# Starter.net
KiCad netlist of a schematic drawn in EAGLE
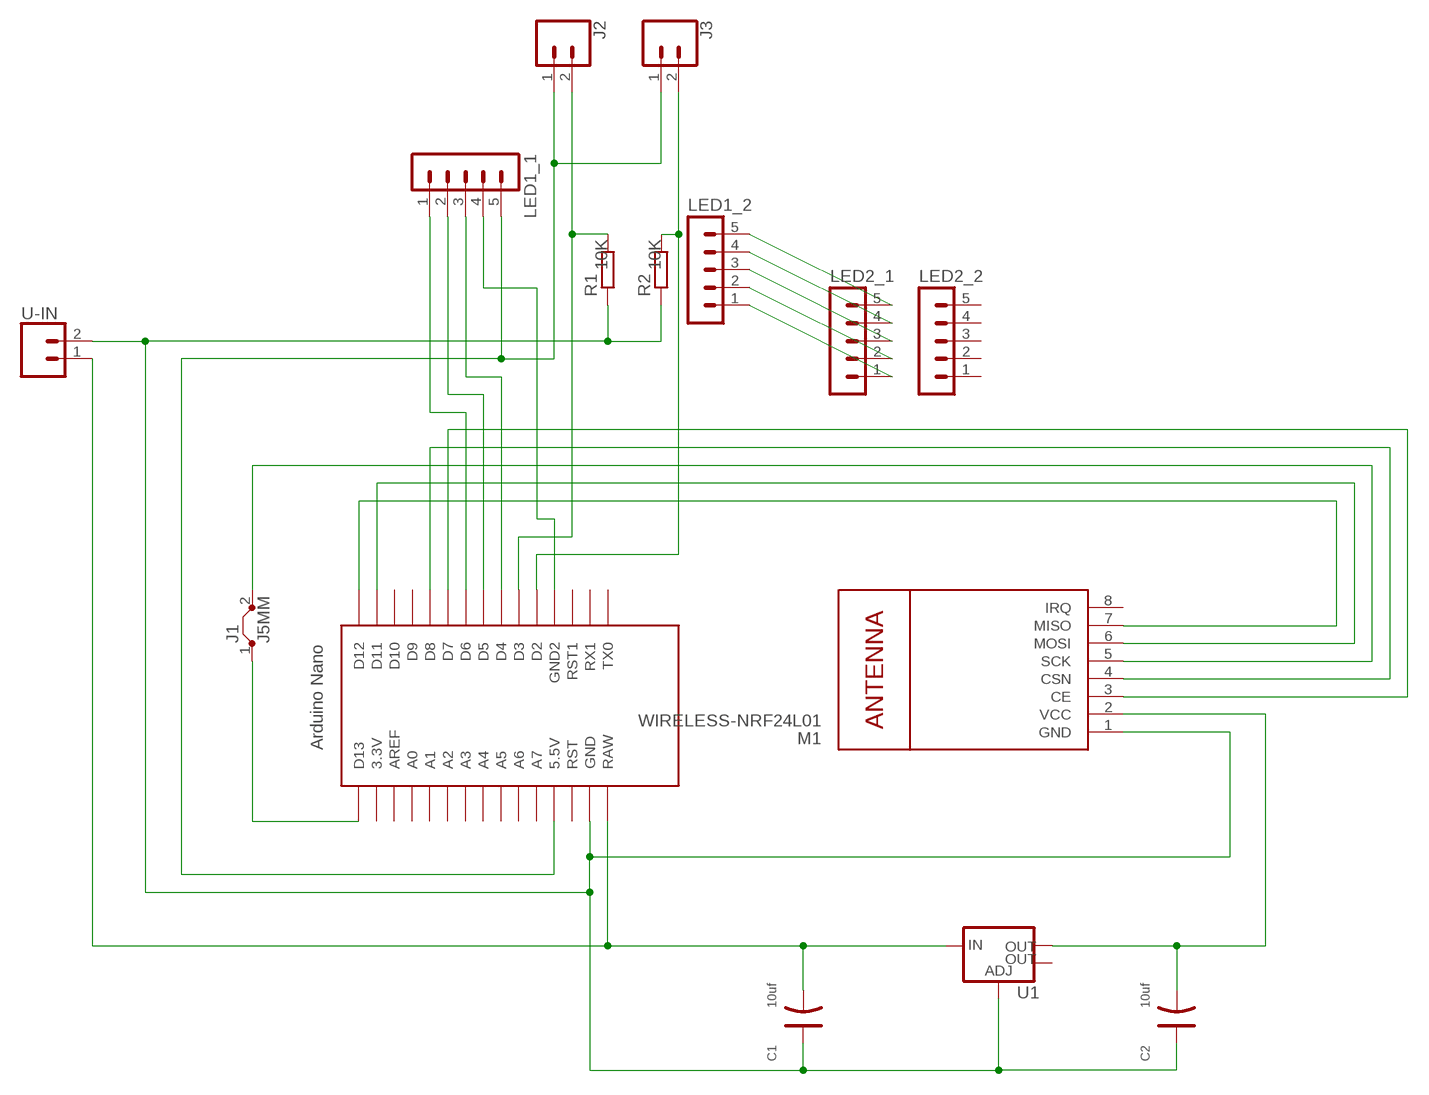
[diagram p0: schematic, sheet 1]

(export (version "E")
  (design (tool "Eeschema 10.0.6"))
  (components
    (comp (ref "C1")
      (value "10uf")
      (footprint "eagle-import:AVX-B")
      (fields (field (name "MPN") "TAJB106K016RNJ"))
      (libsource (lib "eagle-import") (part "TANTALUM-SMD-10UF-16V-10%(AVX-B)"))
    )
    (comp (ref "C2")
      (value "10uf")
      (footprint "eagle-import:AVX-B")
      (fields (field (name "MPN") "TAJB106K016RNJ"))
      (libsource (lib "eagle-import") (part "TANTALUM-SMD-10UF-16V-10%(AVX-B)"))
    )
    (comp (ref "J1")
      (value "J5MM")
      (footprint "eagle-import:05")
      (libsource (lib "eagle-import") (part "J5MM"))
    )
    (comp (ref "J2")
      (value "CONN_025MM")
      (footprint "eagle-import:SCREWTERMINAL-5MM-2")
      (libsource (lib "eagle-import") (part "CONN_025MM"))
    )
    (comp (ref "J3")
      (value "CONN_025MM")
      (footprint "eagle-import:SCREWTERMINAL-5MM-2")
      (libsource (lib "eagle-import") (part "CONN_025MM"))
    )
    (comp (ref "LED1_1")
      (value "MA05-1")
      (footprint "eagle-import:MA05-1")
      (libsource (lib "eagle-import") (part "MA05-1"))
    )
    (comp (ref "LED1_2")
      (value "MA05-1")
      (footprint "eagle-import:MA05-1")
      (libsource (lib "eagle-import") (part "MA05-1"))
    )
    (comp (ref "LED2_1")
      (value "MA05-1")
      (footprint "eagle-import:MA05-1")
      (libsource (lib "eagle-import") (part "MA05-1"))
    )
    (comp (ref "LED2_2")
      (value "MA05-1")
      (footprint "eagle-import:MA05-1")
      (libsource (lib "eagle-import") (part "MA05-1"))
    )
    (comp (ref "M1")
      (value "WIRELESS-NRF24L01")
      (footprint "eagle-import:WIRELESS-NRF24L01")
      (libsource (lib "eagle-import") (part "WIRELESS-NRF24L01"))
    )
    (comp (ref "R1")
      (value "R-EU_0207/12")
      (footprint "eagle-import:0207_12")
      (fields (field (name "R") "10K"))
      (libsource (lib "eagle-import") (part "R-EU_0207/12"))
    )
    (comp (ref "R2")
      (value "R-EU_0207/12")
      (footprint "eagle-import:0207_12")
      (fields (field (name "R") "10K"))
      (libsource (lib "eagle-import") (part "R-EU_0207/12"))
    )
    (comp (ref "U$1")
      (value "NANO")
      (footprint "eagle-import:NANO")
      (libsource (lib "eagle-import") (part "NANO"))
    )
    (comp (ref "U-IN")
      (value "CONN_025MM")
      (footprint "eagle-import:SCREWTERMINAL-5MM-2")
      (libsource (lib "eagle-import") (part "CONN_025MM"))
    )
    (comp (ref "U1")
      (value "V_REG_LM1117SOT223")
      (footprint "eagle-import:SOT223")
      (libsource (lib "eagle-import") (part "V_REG_LM1117SOT223"))
    )
  )
  (nets
    (net (code "1") (name "Net-(J1-Pad1)") (class "Default")
      (node (ref "J1") (pin "1") (pinfunction "1_1") (pintype "passive"))
      (node (ref "U$1") (pin "D13") (pinfunction "D13_D13") (pintype "bidirectional"))
    )
    (net (code "2") (name "Net-(J2-Pad2)") (class "Default")
      (node (ref "J2") (pin "2") (pinfunction "2_2") (pintype "passive"))
      (node (ref "R1") (pin "2") (pinfunction "2_2") (pintype "passive"))
      (node (ref "U$1") (pin "D3") (pinfunction "D3_D3") (pintype "bidirectional"))
    )
    (net (code "3") (name "Net-(J3-Pad2)") (class "Default")
      (node (ref "J3") (pin "2") (pinfunction "2_2") (pintype "passive"))
      (node (ref "R2") (pin "2") (pinfunction "2_2") (pintype "passive"))
      (node (ref "U$1") (pin "D2") (pinfunction "D2_D2") (pintype "bidirectional"))
    )
    (net (code "4") (name "Net-(LED1_1-Pad1)") (class "Default")
      (node (ref "LED1_1") (pin "1") (pinfunction "1_1") (pintype "passive"))
      (node (ref "U$1") (pin "D6") (pinfunction "D6_D6") (pintype "bidirectional"))
    )
    (net (code "5") (name "Net-(LED1_1-Pad2)") (class "Default")
      (node (ref "LED1_1") (pin "2") (pinfunction "2_2") (pintype "passive"))
      (node (ref "U$1") (pin "D5") (pinfunction "D5_D5") (pintype "bidirectional"))
    )
    (net (code "6") (name "Net-(LED1_1-Pad3)") (class "Default")
      (node (ref "LED1_1") (pin "3") (pinfunction "3_3") (pintype "passive"))
      (node (ref "U$1") (pin "D4") (pinfunction "D4_D4") (pintype "bidirectional"))
    )
    (net (code "7") (name "Net-(LED1_2-Pad1)") (class "Default")
      (node (ref "LED1_2") (pin "1") (pinfunction "1_1") (pintype "passive"))
      (node (ref "LED2_1") (pin "1") (pinfunction "1_1") (pintype "passive"))
    )
    (net (code "8") (name "Net-(LED1_2-Pad2)") (class "Default")
      (node (ref "LED1_2") (pin "2") (pinfunction "2_2") (pintype "passive"))
      (node (ref "LED2_1") (pin "2") (pinfunction "2_2") (pintype "passive"))
    )
    (net (code "9") (name "Net-(LED1_2-Pad3)") (class "Default")
      (node (ref "LED1_2") (pin "3") (pinfunction "3_3") (pintype "passive"))
      (node (ref "LED2_1") (pin "3") (pinfunction "3_3") (pintype "passive"))
    )
    (net (code "10") (name "Net-(LED1_2-Pad4)") (class "Default")
      (node (ref "LED1_2") (pin "4") (pinfunction "4_4") (pintype "passive"))
      (node (ref "LED2_1") (pin "4") (pinfunction "4_4") (pintype "passive"))
    )
    (net (code "11") (name "Net-(LED1_2-Pad5)") (class "Default")
      (node (ref "LED1_2") (pin "5") (pinfunction "5_5") (pintype "passive"))
      (node (ref "LED2_1") (pin "5") (pinfunction "5_5") (pintype "passive"))
    )
    (net (code "12") (name "Net-(M1-CE)") (class "Default")
      (node (ref "M1") (pin "3") (pinfunction "CE_3") (pintype "bidirectional"))
      (node (ref "U$1") (pin "D7") (pinfunction "D7_D7") (pintype "bidirectional"))
    )
    (net (code "13") (name "Net-(M1-CSN)") (class "Default")
      (node (ref "M1") (pin "4") (pinfunction "CSN_4") (pintype "bidirectional"))
      (node (ref "U$1") (pin "D8") (pinfunction "D8_D8") (pintype "bidirectional"))
    )
    (net (code "14") (name "Net-(M1-GND)") (class "Default")
      (node (ref "C1") (pin "+") (pinfunction "+_+") (pintype "passive"))
      (node (ref "C2") (pin "+") (pinfunction "+_+") (pintype "passive"))
      (node (ref "M1") (pin "1") (pinfunction "GND_1") (pintype "power_in"))
      (node (ref "R1") (pin "1") (pinfunction "1_1") (pintype "passive"))
      (node (ref "R2") (pin "1") (pinfunction "1_1") (pintype "passive"))
      (node (ref "U$1") (pin "GND") (pinfunction "GND_GND") (pintype "bidirectional"))
      (node (ref "U-IN") (pin "2") (pinfunction "2_2") (pintype "passive"))
      (node (ref "U1") (pin "1") (pinfunction "ADJ_1") (pintype "input"))
    )
    (net (code "15") (name "Net-(M1-MISO)") (class "Default")
      (node (ref "M1") (pin "7") (pinfunction "MISO_7") (pintype "bidirectional"))
      (node (ref "U$1") (pin "D12") (pinfunction "D12_D12") (pintype "bidirectional"))
    )
    (net (code "16") (name "Net-(M1-MOSI)") (class "Default")
      (node (ref "M1") (pin "6") (pinfunction "MOSI_6") (pintype "bidirectional"))
      (node (ref "U$1") (pin "D11") (pinfunction "D11_D11") (pintype "bidirectional"))
    )
    (net (code "17") (name "Net-(M1-SCK)") (class "Default")
      (node (ref "J1") (pin "2") (pinfunction "2_2") (pintype "passive"))
      (node (ref "M1") (pin "5") (pinfunction "SCK_5") (pintype "bidirectional"))
    )
    (net (code "18") (name "Net-(M1-VCC)") (class "Default")
      (node (ref "C2") (pin "-") (pinfunction "-_-") (pintype "passive"))
      (node (ref "M1") (pin "2") (pinfunction "VCC_2") (pintype "power_in"))
      (node (ref "U1") (pin "2") (pinfunction "OUT_2") (pintype "output"))
    )
    (net (code "19") (name "Net-(U$1-5.5V)") (class "Default")
      (node (ref "J2") (pin "1") (pinfunction "1_1") (pintype "passive"))
      (node (ref "J3") (pin "1") (pinfunction "1_1") (pintype "passive"))
      (node (ref "LED1_1") (pin "5") (pinfunction "5_5") (pintype "passive"))
      (node (ref "U$1") (pin "5V") (pinfunction "5.5V_5V") (pintype "bidirectional"))
    )
    (net (code "20") (name "Net-(U$1-GND2)") (class "Default")
      (node (ref "LED1_1") (pin "4") (pinfunction "4_4") (pintype "passive"))
      (node (ref "U$1") (pin "GND1") (pinfunction "GND2_GND1") (pintype "bidirectional"))
    )
    (net (code "21") (name "Net-(U1-IN)") (class "Default")
      (node (ref "C1") (pin "-") (pinfunction "-_-") (pintype "passive"))
      (node (ref "U$1") (pin "RAW") (pinfunction "RAW_RAW") (pintype "bidirectional"))
      (node (ref "U-IN") (pin "1") (pinfunction "1_1") (pintype "passive"))
      (node (ref "U1") (pin "3") (pinfunction "IN_3") (pintype "input"))
    )
    (net (code "22") (name "unconnected-(LED2_2-Pad1)") (class "Default")
      (node (ref "LED2_2") (pin "1") (pinfunction "1_1") (pintype "passive"))
    )
    (net (code "23") (name "unconnected-(LED2_2-Pad2)") (class "Default")
      (node (ref "LED2_2") (pin "2") (pinfunction "2_2") (pintype "passive"))
    )
    (net (code "24") (name "unconnected-(LED2_2-Pad3)") (class "Default")
      (node (ref "LED2_2") (pin "3") (pinfunction "3_3") (pintype "passive"))
    )
    (net (code "25") (name "unconnected-(LED2_2-Pad4)") (class "Default")
      (node (ref "LED2_2") (pin "4") (pinfunction "4_4") (pintype "passive"))
    )
    (net (code "26") (name "unconnected-(LED2_2-Pad5)") (class "Default")
      (node (ref "LED2_2") (pin "5") (pinfunction "5_5") (pintype "passive"))
    )
    (net (code "27") (name "unconnected-(M1-IRQ-Pad8)") (class "Default")
      (node (ref "M1") (pin "8") (pinfunction "IRQ_8") (pintype "bidirectional"))
    )
    (net (code "28") (name "unconnected-(U$1-Pad3.3V)") (class "Default")
      (node (ref "U$1") (pin "3.3V") (pinfunction "3.3V_3.3V") (pintype "bidirectional"))
    )
    (net (code "29") (name "unconnected-(U$1-PadA0)") (class "Default")
      (node (ref "U$1") (pin "A0") (pinfunction "A0_A0") (pintype "bidirectional"))
    )
    (net (code "30") (name "unconnected-(U$1-PadA1)") (class "Default")
      (node (ref "U$1") (pin "A1") (pinfunction "A1_A1") (pintype "bidirectional"))
    )
    (net (code "31") (name "unconnected-(U$1-PadA2)") (class "Default")
      (node (ref "U$1") (pin "A2") (pinfunction "A2_A2") (pintype "bidirectional"))
    )
    (net (code "32") (name "unconnected-(U$1-PadA3)") (class "Default")
      (node (ref "U$1") (pin "A3") (pinfunction "A3_A3") (pintype "bidirectional"))
    )
    (net (code "33") (name "unconnected-(U$1-PadA4)") (class "Default")
      (node (ref "U$1") (pin "A4") (pinfunction "A4_A4") (pintype "bidirectional"))
    )
    (net (code "34") (name "unconnected-(U$1-PadA5)") (class "Default")
      (node (ref "U$1") (pin "A5") (pinfunction "A5_A5") (pintype "bidirectional"))
    )
    (net (code "35") (name "unconnected-(U$1-PadA6)") (class "Default")
      (node (ref "U$1") (pin "A6") (pinfunction "A6_A6") (pintype "bidirectional"))
    )
    (net (code "36") (name "unconnected-(U$1-PadA7)") (class "Default")
      (node (ref "U$1") (pin "A7") (pinfunction "A7_A7") (pintype "bidirectional"))
    )
    (net (code "37") (name "unconnected-(U$1-PadAREF)") (class "Default")
      (node (ref "U$1") (pin "AREF") (pinfunction "AREF_AREF") (pintype "bidirectional"))
    )
    (net (code "38") (name "unconnected-(U$1-PadD9)") (class "Default")
      (node (ref "U$1") (pin "D9") (pinfunction "D9_D9") (pintype "bidirectional"))
    )
    (net (code "39") (name "unconnected-(U$1-PadD10)") (class "Default")
      (node (ref "U$1") (pin "D10") (pinfunction "D10_D10") (pintype "bidirectional"))
    )
    (net (code "40") (name "unconnected-(U$1-PadICSP1)") (class "Default")
      (node (ref "U$1") (pin "ICSP1") (pinfunction "ICSP1_ICSP1") (pintype "bidirectional"))
    )
    (net (code "41") (name "unconnected-(U$1-PadICSP2)") (class "Default")
      (node (ref "U$1") (pin "ICSP2") (pinfunction "ICSP2_ICSP2") (pintype "bidirectional"))
    )
    (net (code "42") (name "unconnected-(U$1-PadICSP3)") (class "Default")
      (node (ref "U$1") (pin "ICSP3") (pinfunction "ICSP3_ICSP3") (pintype "bidirectional"))
    )
    (net (code "43") (name "unconnected-(U$1-PadICSP4)") (class "Default")
      (node (ref "U$1") (pin "ICSP4") (pinfunction "ICSP4_ICSP4") (pintype "bidirectional"))
    )
    (net (code "44") (name "unconnected-(U$1-PadICSP5)") (class "Default")
      (node (ref "U$1") (pin "ICSP5") (pinfunction "ICSP5_ICSP5") (pintype "bidirectional"))
    )
    (net (code "45") (name "unconnected-(U$1-PadICSP6)") (class "Default")
      (node (ref "U$1") (pin "ICSP6") (pinfunction "ICSP6_ICSP6") (pintype "bidirectional"))
    )
    (net (code "46") (name "unconnected-(U$1-PadRST)") (class "Default")
      (node (ref "U$1") (pin "RST") (pinfunction "RST_RST") (pintype "bidirectional"))
    )
    (net (code "47") (name "unconnected-(U$1-PadRST1)") (class "Default")
      (node (ref "U$1") (pin "RST1") (pinfunction "RST1_RST1") (pintype "bidirectional"))
    )
    (net (code "48") (name "unconnected-(U$1-PadRX1)") (class "Default")
      (node (ref "U$1") (pin "RX1") (pinfunction "RX1_RX1") (pintype "bidirectional"))
    )
    (net (code "49") (name "unconnected-(U$1-PadTX0)") (class "Default")
      (node (ref "U$1") (pin "TX0") (pinfunction "TX0_TX0") (pintype "bidirectional"))
    )
    (net (code "50") (name "unconnected-(U1-OUT-Pad4)") (class "Default")
      (node (ref "U1") (pin "4") (pinfunction "OUT_4") (pintype "output"))
    )
  )
)
